# 06_LED_OUTPUTS.net
KiCad netlist of a schematic drawn in Altium Designer
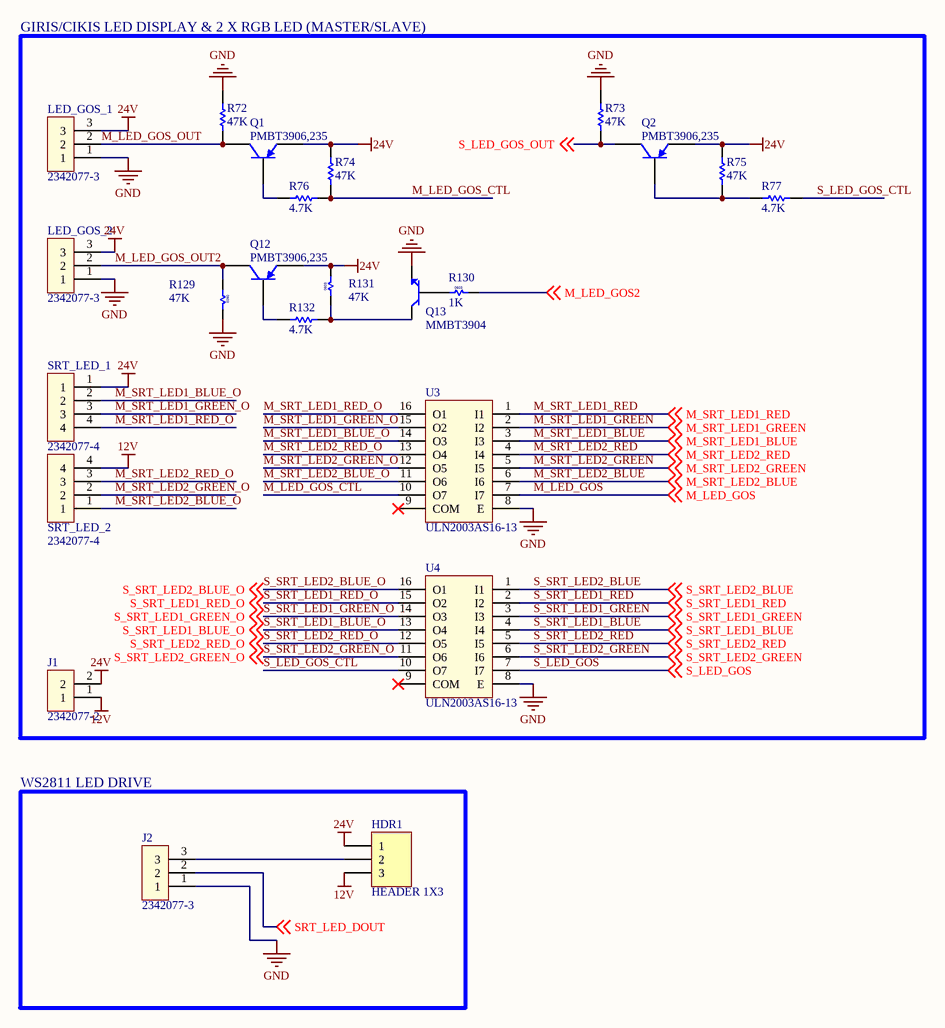
[diagram p0: 06_LED_OUTPUTS.SchDoc]

(export (version "E")
  (design (tool "Eeschema 10.0.6"))
  (components
    (comp (ref "HDR1")
      (value "HEADER 1X3")
      (footprint "HDR1X3")
      (description "Header, 3-Pin")
      (fields (field (name "PUBLISHER") "Altium Limited"))
      (libsource (lib "FKDZ_Altium_Lib") (part "HEADER 1X3"))
    )
    (comp (ref "J1")
      (value "2342077-2")
      (footprint "TERM BLOCK HDR 2POS 90DEG PITCH 3.81MM")
      (fields
        (field (name "DIGI-KEY PART NUMBER") "A145321-ND")
        (field (name "MANUFACTURER") "TE Connectivity AMP Connectors")
      )
      (libsource (lib "FKDZ_Altium_Lib") (part "TERM BLOCK HDR 2POS 90DEG 3.81MM"))
    )
    (comp (ref "J2")
      (value "2342077-3")
      (footprint "TERM BLOCK HDR 3POS 90DEG PITCH 3.81MM")
      (fields
        (field (name "DIGI-KEY PART NUMBER") "A145322-ND")
        (field (name "MANUFACTURER") "TE Connectivity AMP Connectors")
      )
      (libsource (lib "FKDZ_Altium_Lib") (part "TERM BLOCK HDR 3POS 90DEG 3.81MM"))
    )
    (comp (ref "LED_GOS_1")
      (value "2342077-3")
      (footprint "TERM BLOCK HDR 3POS 90DEG PITCH 3.81MM")
      (fields
        (field (name "DIGI-KEY PART NUMBER") "A145322-ND")
        (field (name "MANUFACTURER") "TE Connectivity AMP Connectors")
      )
      (libsource (lib "FKDZ_Altium_Lib") (part "TERM BLOCK HDR 3POS 90DEG 3.81MM"))
    )
    (comp (ref "LED_GOS_2")
      (value "2342077-3")
      (footprint "TERM BLOCK HDR 3POS 90DEG PITCH 3.81MM")
      (fields
        (field (name "DIGI-KEY PART NUMBER") "A145322-ND")
        (field (name "MANUFACTURER") "TE Connectivity AMP Connectors")
      )
      (libsource (lib "FKDZ_Altium_Lib") (part "TERM BLOCK HDR 3POS 90DEG 3.81MM"))
    )
    (comp (ref "Q1")
      (value "PMBT3906,235")
      (footprint "ONSC-SOT-23-3-318-08_V")
      (description "Bipolar (BJT) Transistor PNP 40 V 200 mA 250MHz 250 mW Surface Mount TO-236AB")
      (fields (field (name "DIGI-KEY PART NUMBER") "1727-1885-1-ND"))
      (libsource (lib "FKDZ_Altium_Lib") (part "TRANS PNP 40V 200MA TO236AB PMBT3906_235"))
    )
    (comp (ref "Q2")
      (value "PMBT3906,235")
      (footprint "ONSC-SOT-23-3-318-08_V")
      (description "Bipolar (BJT) Transistor PNP 40 V 200 mA 250MHz 250 mW Surface Mount TO-236AB")
      (fields (field (name "DIGI-KEY PART NUMBER") "1727-1885-1-ND"))
      (libsource (lib "FKDZ_Altium_Lib") (part "TRANS PNP 40V 200MA TO236AB PMBT3906_235"))
    )
    (comp (ref "Q12")
      (value "PMBT3906,235")
      (footprint "ONSC-SOT-23-3-318-08_V")
      (description "Bipolar (BJT) Transistor PNP 40 V 200 mA 250MHz 250 mW Surface Mount TO-236AB")
      (fields (field (name "DIGI-KEY PART NUMBER") "1727-1885-1-ND"))
      (libsource (lib "FKDZ_Altium_Lib") (part "TRANS PNP 40V 200MA TO236AB PMBT3906_235"))
    )
    (comp (ref "Q13")
      (value "MMBT3904")
      (footprint "ONSC-SOT-23-3-318-08_V")
      (description "Bipolar (BJT) Transistor NPN 40V 200mA 300MHz 300mW Surface Mount SOT-23-3 (TO-236)")
      (fields
        (field (name "DIGI-KEY PART NUMBER") "MMBT3904LT3GOSTR-ND")
        (field (name "MANUFACTURER") "ON Semiconductor")
      )
      (libsource (lib "FKDZ_Altium_Lib") (part "NPN_BT3904"))
    )
    (comp (ref "R72")
      (value "47K")
      (footprint "603R")
      (description "47 kOhms ±1% 0.1W, 1/10W Chip Resistor 0603 (1608 Metric)  Thick Film")
      (fields (field (name "DIGI-KEY PART NUMBER") "311-47.0KHRCT-ND") (field (name "MANUFACTURER") "Yageo"))
      (libsource (lib "FKDZ_Altium_Lib") (part "RES SMD 47K OHM 1% 1/10W 0603"))
    )
    (comp (ref "R73")
      (value "47K")
      (footprint "603R")
      (description "47 kOhms ±1% 0.1W, 1/10W Chip Resistor 0603 (1608 Metric)  Thick Film")
      (fields (field (name "DIGI-KEY PART NUMBER") "311-47.0KHRCT-ND") (field (name "MANUFACTURER") "Yageo"))
      (libsource (lib "FKDZ_Altium_Lib") (part "RES SMD 47K OHM 1% 1/10W 0603"))
    )
    (comp (ref "R74")
      (value "47K")
      (footprint "603R")
      (description "47 kOhms ±1% 0.1W, 1/10W Chip Resistor 0603 (1608 Metric)  Thick Film")
      (fields (field (name "DIGI-KEY PART NUMBER") "311-47.0KHRCT-ND") (field (name "MANUFACTURER") "Yageo"))
      (libsource (lib "FKDZ_Altium_Lib") (part "RES SMD 47K OHM 1% 1/10W 0603"))
    )
    (comp (ref "R75")
      (value "47K")
      (footprint "603R")
      (description "47 kOhms ±1% 0.1W, 1/10W Chip Resistor 0603 (1608 Metric)  Thick Film")
      (fields (field (name "DIGI-KEY PART NUMBER") "311-47.0KHRCT-ND") (field (name "MANUFACTURER") "Yageo"))
      (libsource (lib "FKDZ_Altium_Lib") (part "RES SMD 47K OHM 1% 1/10W 0603"))
    )
    (comp (ref "R76")
      (value "4.7K")
      (footprint "603R")
      (description "4.7 kOhms ±5% 0.1W, 1/10W Chip Resistor 0603 (1608 Metric) Moisture Resistant Thick Film")
      (fields (field (name "DIGI-KEY PART NUMBER") "311-4.7KGRTR-ND") (field (name "MANUFACTURER") "Yageo"))
      (libsource (lib "FKDZ_Altium_Lib") (part "RES_4.7K_OHM_%5_0.1W_0603"))
    )
    (comp (ref "R77")
      (value "4.7K")
      (footprint "603R")
      (description "4.7 kOhms ±5% 0.1W, 1/10W Chip Resistor 0603 (1608 Metric) Moisture Resistant Thick Film")
      (fields (field (name "DIGI-KEY PART NUMBER") "311-4.7KGRTR-ND") (field (name "MANUFACTURER") "Yageo"))
      (libsource (lib "FKDZ_Altium_Lib") (part "RES_4.7K_OHM_%5_0.1W_0603"))
    )
    (comp (ref "R129")
      (value "47K")
      (footprint "603R")
      (description "47 kOhms ±5% 0.1W, 1/10W Chip Resistor 0603 (1608 Metric) Moisture Resistant Thick Film")
      (fields (field (name "DIGI-KEY PART NUMBER") "311-47KGRTR-ND") (field (name "MANUFACTURER") "Yageo"))
      (libsource (lib "FKDZ_Altium_Lib") (part "RES_47K_OHM_%5_0.1W_0603"))
    )
    (comp (ref "R130")
      (value "1K")
      (footprint "603R")
      (description "1 kOhms ±5% 0.1W, 1/10W Chip Resistor 0603 (1608 Metric) Moisture Resistant Thick Film")
      (fields (field (name "DIGI-KEY PART NUMBER") "311-1.0KGRTR-ND") (field (name "MANUFACTURER") "Yageo"))
      (libsource (lib "FKDZ_Altium_Lib") (part "RES_1K_OHM_%5_0.1W_0603"))
    )
    (comp (ref "R131")
      (value "47K")
      (footprint "603R")
      (description "47 kOhms ±5% 0.1W, 1/10W Chip Resistor 0603 (1608 Metric) Moisture Resistant Thick Film")
      (fields (field (name "DIGI-KEY PART NUMBER") "311-47KGRTR-ND") (field (name "MANUFACTURER") "Yageo"))
      (libsource (lib "FKDZ_Altium_Lib") (part "RES_47K_OHM_%5_0.1W_0603"))
    )
    (comp (ref "R132")
      (value "4.7K")
      (footprint "603R")
      (description "4.7 kOhms ±5% 0.1W, 1/10W Chip Resistor 0603 (1608 Metric) Moisture Resistant Thick Film")
      (fields (field (name "DIGI-KEY PART NUMBER") "311-4.7KGRTR-ND") (field (name "MANUFACTURER") "Yageo"))
      (libsource (lib "FKDZ_Altium_Lib") (part "RES_4.7K_OHM_%5_0.1W_0603"))
    )
    (comp (ref "SRT_LED_1")
      (value "2342077-4")
      (footprint "TERM BLOCK HDR 4POS 90DEG PITCH 3.81MM")
      (fields
        (field (name "DIGI-KEY PART NUMBER") "A145323-ND")
        (field (name "MANUFACTURER") "TE Connectivity AMP Connectors")
      )
      (libsource (lib "") (part "TERM BLOCK HDR 4POS 90DEG 3.81MM_1"))
    )
    (comp (ref "SRT_LED_2")
      (value "2342077-4")
      (footprint "TERM BLOCK HDR 4POS 90DEG PITCH 3.81MM")
      (fields
        (field (name "DIGI-KEY PART NUMBER") "A145323-ND")
        (field (name "MANUFACTURER") "TE Connectivity AMP Connectors")
      )
      (libsource (lib "FKDZ_Altium_Lib") (part "TERM BLOCK HDR 4POS 90DEG 3.81MM"))
    )
    (comp (ref "U3")
      (value "ULN2003AS16-13")
      (footprint "SO16")
      (description "Bipolar (BJT) Transistor Array 7 NPN Darlington 50V 500mA - - Surface Mount 16-SO")
      (fields
        (field (name "DIGI-KEY PART NUMBER") "ULN2003AS16-13DICT-ND")
        (field (name "MANUFACTURER") "Diodes Incorporated")
      )
      (libsource (lib "FKDZ_Altium_Lib") (part "IC PWR RELAY 7NPN 1{colon}1 16SO ULN2003AS16-13"))
    )
    (comp (ref "U4")
      (value "ULN2003AS16-13")
      (footprint "SO16")
      (description "Bipolar (BJT) Transistor Array 7 NPN Darlington 50V 500mA - - Surface Mount 16-SO")
      (fields
        (field (name "DIGI-KEY PART NUMBER") "ULN2003AS16-13DICT-ND")
        (field (name "MANUFACTURER") "Diodes Incorporated")
      )
      (libsource (lib "FKDZ_Altium_Lib") (part "IC PWR RELAY 7NPN 1{colon}1 16SO ULN2003AS16-13"))
    )
  )
  (nets
    (net (code "1") (name "/M_LED_GOS_CTL") (class "Default")
      (node (ref "R74") (pin "1") (pinfunction "1_1") (pintype "passive"))
      (node (ref "R76") (pin "1") (pinfunction "1_1") (pintype "passive"))
      (node (ref "U3") (pin "10") (pinfunction "O7_10") (pintype "passive"))
    )
    (net (code "2") (name "/M_LED_GOS_OUT") (class "Default")
      (node (ref "LED_GOS_1") (pin "2") (pinfunction "2_2") (pintype "passive"))
      (node (ref "Q1") (pin "3") (pinfunction "C_3") (pintype "passive"))
      (node (ref "R72") (pin "2") (pinfunction "2_2") (pintype "passive"))
    )
    (net (code "3") (name "/M_LED_GOS_OUT2") (class "Default")
      (node (ref "LED_GOS_2") (pin "2") (pinfunction "2_2") (pintype "passive"))
      (node (ref "Q12") (pin "3") (pinfunction "C_3") (pintype "passive"))
      (node (ref "R129") (pin "1") (pinfunction "1_1") (pintype "passive"))
    )
    (net (code "4") (name "/M_SRT_LED1_BLUE_O") (class "Default")
      (node (ref "SRT_LED_1") (pin "2") (pinfunction "2_2") (pintype "passive"))
      (node (ref "U3") (pin "14") (pinfunction "O3_14") (pintype "passive"))
    )
    (net (code "5") (name "/M_SRT_LED1_GREEN_O") (class "Default")
      (node (ref "SRT_LED_1") (pin "3") (pinfunction "3_3") (pintype "passive"))
      (node (ref "U3") (pin "15") (pinfunction "O2_15") (pintype "passive"))
    )
    (net (code "6") (name "/M_SRT_LED1_RED_O") (class "Default")
      (node (ref "SRT_LED_1") (pin "4") (pinfunction "4_4") (pintype "passive"))
      (node (ref "U3") (pin "16") (pinfunction "O1_16") (pintype "passive"))
    )
    (net (code "7") (name "/M_SRT_LED2_BLUE_O") (class "Default")
      (node (ref "SRT_LED_2") (pin "1") (pinfunction "1_1") (pintype "passive"))
      (node (ref "U3") (pin "11") (pinfunction "O6_11") (pintype "passive"))
    )
    (net (code "8") (name "/M_SRT_LED2_GREEN_O") (class "Default")
      (node (ref "SRT_LED_2") (pin "2") (pinfunction "2_2") (pintype "passive"))
      (node (ref "U3") (pin "12") (pinfunction "O5_12") (pintype "passive"))
    )
    (net (code "9") (name "/M_SRT_LED2_RED_O") (class "Default")
      (node (ref "SRT_LED_2") (pin "3") (pinfunction "3_3") (pintype "passive"))
      (node (ref "U3") (pin "13") (pinfunction "O4_13") (pintype "passive"))
    )
    (net (code "10") (name "/S_LED_GOS_CTL") (class "Default")
      (node (ref "R77") (pin "1") (pinfunction "1_1") (pintype "passive"))
      (node (ref "U4") (pin "10") (pinfunction "O7_10") (pintype "passive"))
    )
    (net (code "11") (name "12V") (class "Default")
      (node (ref "HDR1") (pin "3") (pinfunction "3_3") (pintype "passive"))
      (node (ref "J1") (pin "1") (pinfunction "1_1") (pintype "passive"))
      (node (ref "SRT_LED_2") (pin "4") (pinfunction "4_4") (pintype "passive"))
    )
    (net (code "12") (name "24V") (class "Default")
      (node (ref "HDR1") (pin "1") (pinfunction "1_1") (pintype "passive"))
      (node (ref "J1") (pin "2") (pinfunction "2_2") (pintype "passive"))
      (node (ref "LED_GOS_1") (pin "3") (pinfunction "3_3") (pintype "passive"))
      (node (ref "LED_GOS_2") (pin "3") (pinfunction "3_3") (pintype "passive"))
      (node (ref "Q1") (pin "2") (pinfunction "E_2") (pintype "passive"))
      (node (ref "Q12") (pin "2") (pinfunction "E_2") (pintype "passive"))
      (node (ref "Q2") (pin "2") (pinfunction "E_2") (pintype "passive"))
      (node (ref "R131") (pin "2") (pinfunction "2_2") (pintype "passive"))
      (node (ref "R74") (pin "2") (pinfunction "2_2") (pintype "passive"))
      (node (ref "R75") (pin "2") (pinfunction "2_2") (pintype "passive"))
      (node (ref "SRT_LED_1") (pin "1") (pinfunction "1_1") (pintype "passive"))
    )
    (net (code "13") (name "GND") (class "Default")
      (node (ref "J2") (pin "1") (pinfunction "1_1") (pintype "passive"))
      (node (ref "LED_GOS_1") (pin "1") (pinfunction "1_1") (pintype "passive"))
      (node (ref "LED_GOS_2") (pin "1") (pinfunction "1_1") (pintype "passive"))
      (node (ref "Q13") (pin "2") (pinfunction "E_2") (pintype "passive"))
      (node (ref "R129") (pin "2") (pinfunction "2_2") (pintype "passive"))
      (node (ref "R72") (pin "1") (pinfunction "1_1") (pintype "passive"))
      (node (ref "R73") (pin "1") (pinfunction "1_1") (pintype "passive"))
      (node (ref "U3") (pin "8") (pinfunction "E_8") (pintype "passive"))
      (node (ref "U4") (pin "8") (pinfunction "E_8") (pintype "passive"))
    )
    (net (code "14") (name "M_LED_GOS") (class "Default")
      (node (ref "U3") (pin "7") (pinfunction "I7_7") (pintype "passive"))
    )
    (net (code "15") (name "M_LED_GOS2") (class "Default")
      (node (ref "R130") (pin "2") (pinfunction "2_2") (pintype "passive"))
    )
    (net (code "16") (name "M_SRT_LED1_BLUE") (class "Default")
      (node (ref "U3") (pin "3") (pinfunction "I3_3") (pintype "passive"))
    )
    (net (code "17") (name "M_SRT_LED1_GREEN") (class "Default")
      (node (ref "U3") (pin "2") (pinfunction "I2_2") (pintype "passive"))
    )
    (net (code "18") (name "M_SRT_LED1_RED") (class "Default")
      (node (ref "U3") (pin "1") (pinfunction "I1_1") (pintype "passive"))
    )
    (net (code "19") (name "M_SRT_LED2_BLUE") (class "Default")
      (node (ref "U3") (pin "6") (pinfunction "I6_6") (pintype "passive"))
    )
    (net (code "20") (name "M_SRT_LED2_GREEN") (class "Default")
      (node (ref "U3") (pin "5") (pinfunction "I5_5") (pintype "passive"))
    )
    (net (code "21") (name "M_SRT_LED2_RED") (class "Default")
      (node (ref "U3") (pin "4") (pinfunction "I4_4") (pintype "passive"))
    )
    (net (code "22") (name "Net-(HDR1-Pad2)") (class "Default")
      (node (ref "HDR1") (pin "2") (pinfunction "2_2") (pintype "passive"))
      (node (ref "J2") (pin "3") (pinfunction "3_3") (pintype "passive"))
    )
    (net (code "23") (name "Net-(Q1-B)") (class "Default")
      (node (ref "Q1") (pin "1") (pinfunction "B_1") (pintype "passive"))
      (node (ref "R76") (pin "2") (pinfunction "2_2") (pintype "passive"))
    )
    (net (code "24") (name "Net-(Q2-B)") (class "Default")
      (node (ref "Q2") (pin "1") (pinfunction "B_1") (pintype "passive"))
      (node (ref "R75") (pin "1") (pinfunction "1_1") (pintype "passive"))
      (node (ref "R77") (pin "2") (pinfunction "2_2") (pintype "passive"))
    )
    (net (code "25") (name "Net-(Q12-B)") (class "Default")
      (node (ref "Q12") (pin "1") (pinfunction "B_1") (pintype "passive"))
      (node (ref "R132") (pin "2") (pinfunction "2_2") (pintype "passive"))
    )
    (net (code "26") (name "Net-(Q13-B)") (class "Default")
      (node (ref "Q13") (pin "1") (pinfunction "B_1") (pintype "passive"))
      (node (ref "R130") (pin "1") (pinfunction "1_1") (pintype "passive"))
    )
    (net (code "27") (name "Net-(Q13-C)") (class "Default")
      (node (ref "Q13") (pin "3") (pinfunction "C_3") (pintype "passive"))
      (node (ref "R131") (pin "1") (pinfunction "1_1") (pintype "passive"))
      (node (ref "R132") (pin "1") (pinfunction "1_1") (pintype "passive"))
    )
    (net (code "28") (name "SRT_LED_DOUT") (class "Default")
      (node (ref "J2") (pin "2") (pinfunction "2_2") (pintype "passive"))
    )
    (net (code "29") (name "S_LED_GOS") (class "Default")
      (node (ref "U4") (pin "7") (pinfunction "I7_7") (pintype "passive"))
    )
    (net (code "30") (name "S_LED_GOS_OUT") (class "Default")
      (node (ref "Q2") (pin "3") (pinfunction "C_3") (pintype "passive"))
      (node (ref "R73") (pin "2") (pinfunction "2_2") (pintype "passive"))
    )
    (net (code "31") (name "S_SRT_LED1_BLUE") (class "Default")
      (node (ref "U4") (pin "4") (pinfunction "I4_4") (pintype "passive"))
    )
    (net (code "32") (name "S_SRT_LED1_BLUE_O") (class "Default")
      (node (ref "U4") (pin "13") (pinfunction "O4_13") (pintype "passive"))
    )
    (net (code "33") (name "S_SRT_LED1_GREEN") (class "Default")
      (node (ref "U4") (pin "3") (pinfunction "I3_3") (pintype "passive"))
    )
    (net (code "34") (name "S_SRT_LED1_GREEN_O") (class "Default")
      (node (ref "U4") (pin "14") (pinfunction "O3_14") (pintype "passive"))
    )
    (net (code "35") (name "S_SRT_LED1_RED") (class "Default")
      (node (ref "U4") (pin "2") (pinfunction "I2_2") (pintype "passive"))
    )
    (net (code "36") (name "S_SRT_LED1_RED_O") (class "Default")
      (node (ref "U4") (pin "15") (pinfunction "O2_15") (pintype "passive"))
    )
    (net (code "37") (name "S_SRT_LED2_BLUE") (class "Default")
      (node (ref "U4") (pin "1") (pinfunction "I1_1") (pintype "passive"))
    )
    (net (code "38") (name "S_SRT_LED2_BLUE_O") (class "Default")
      (node (ref "U4") (pin "16") (pinfunction "O1_16") (pintype "passive"))
    )
    (net (code "39") (name "S_SRT_LED2_GREEN") (class "Default")
      (node (ref "U4") (pin "6") (pinfunction "I6_6") (pintype "passive"))
    )
    (net (code "40") (name "S_SRT_LED2_GREEN_O") (class "Default")
      (node (ref "U4") (pin "11") (pinfunction "O6_11") (pintype "passive"))
    )
    (net (code "41") (name "S_SRT_LED2_RED") (class "Default")
      (node (ref "U4") (pin "5") (pinfunction "I5_5") (pintype "passive"))
    )
    (net (code "42") (name "S_SRT_LED2_RED_O") (class "Default")
      (node (ref "U4") (pin "12") (pinfunction "O5_12") (pintype "passive"))
    )
    (net (code "43") (name "unconnected-(U3-COM-Pad9)") (class "Default")
      (node (ref "U3") (pin "9") (pinfunction "COM_9") (pintype "passive+no_connect"))
    )
    (net (code "44") (name "unconnected-(U4-COM-Pad9)") (class "Default")
      (node (ref "U4") (pin "9") (pinfunction "COM_9") (pintype "passive+no_connect"))
    )
  )
)
